# eDuinoUno.net
KiCad netlist of a schematic drawn in EAGLE
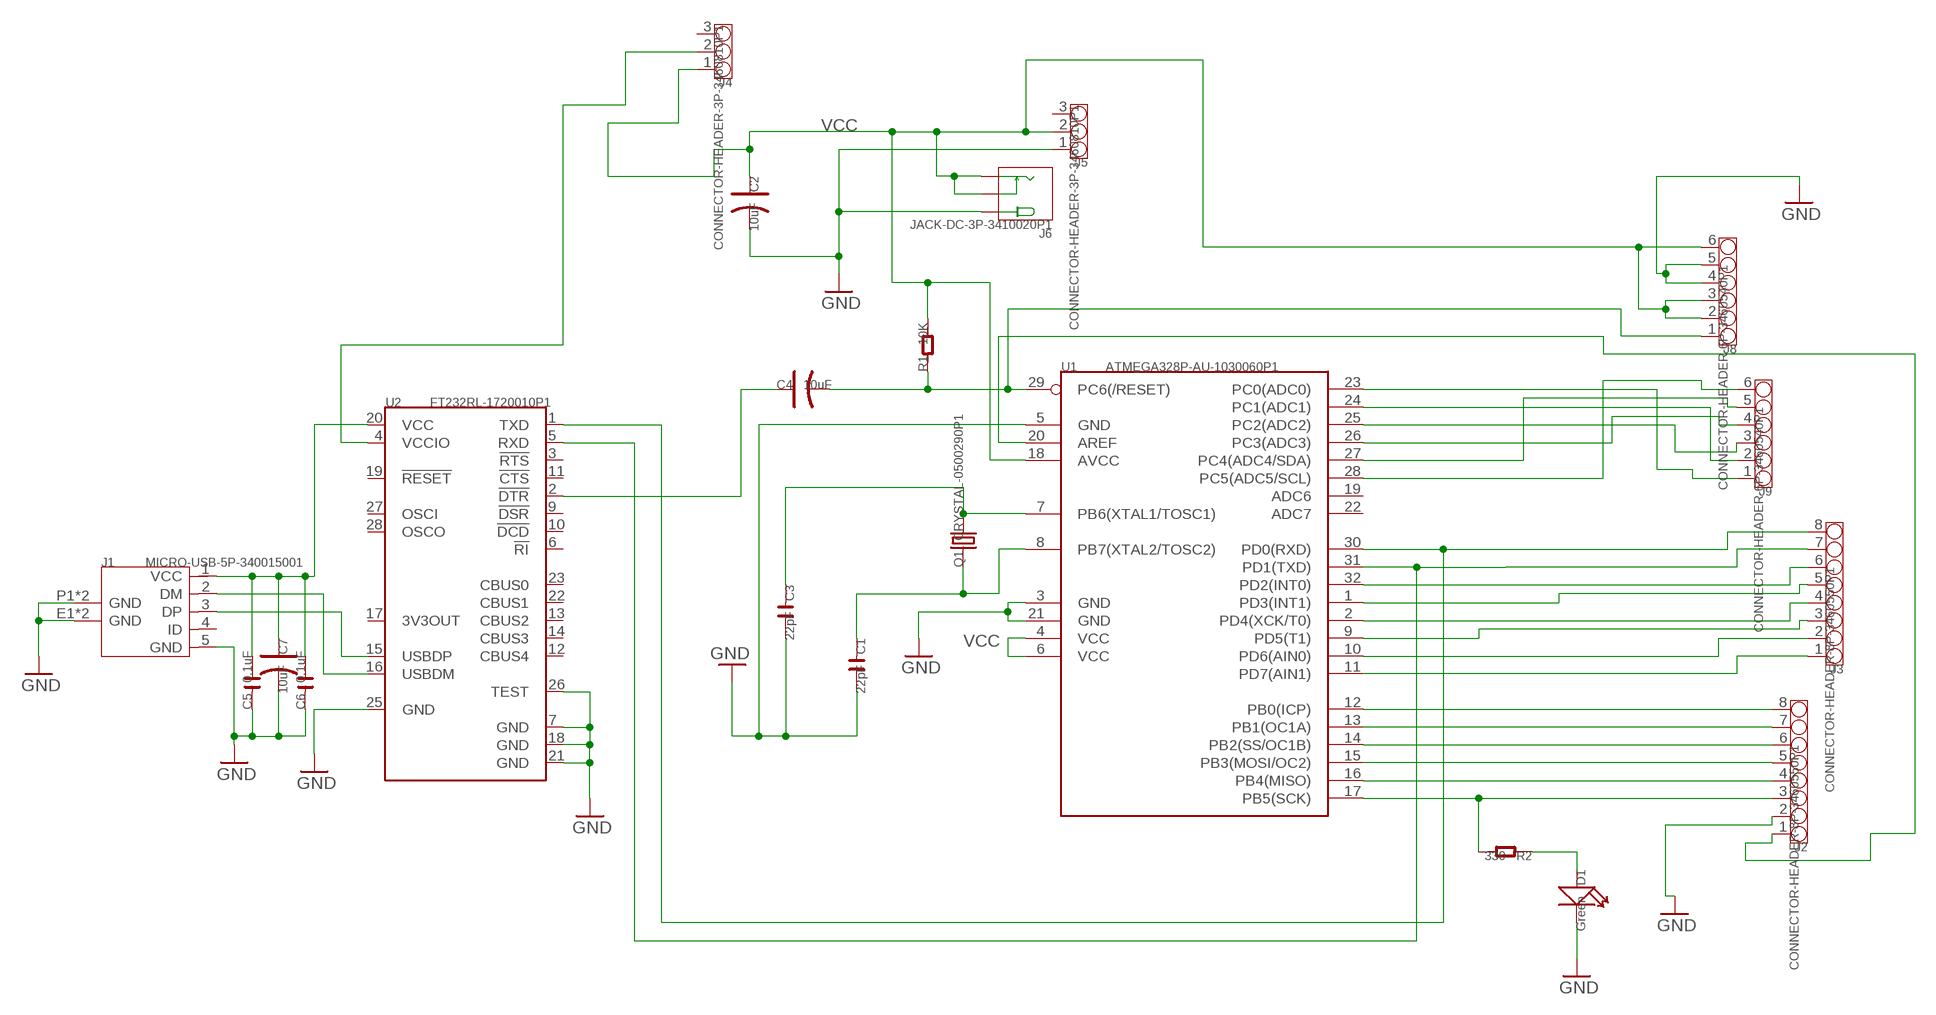
[diagram p0: schematic, sheet 1]

(export (version "E")
  (design (tool "Eeschema 10.0.6"))
  (components
    (comp (ref "C1")
      (value "22pF")
      (footprint "eagle-import:C0603")
      (libsource (lib "eagle-import") (part "C-0603"))
    )
    (comp (ref "C2")
      (value "10uF")
      (footprint "eagle-import:AVX-A")
      (libsource (lib "eagle-import") (part "C-POLAR-A"))
    )
    (comp (ref "C3")
      (value "22pF")
      (footprint "eagle-import:C0603")
      (libsource (lib "eagle-import") (part "C-0603"))
    )
    (comp (ref "C4")
      (value "10uF")
      (footprint "eagle-import:AVX-A")
      (libsource (lib "eagle-import") (part "C-POLAR-A"))
    )
    (comp (ref "C5")
      (value "0.1uF")
      (footprint "eagle-import:C0603")
      (libsource (lib "eagle-import") (part "C-0603"))
    )
    (comp (ref "C6")
      (value "0.1uF")
      (footprint "eagle-import:C0603")
      (libsource (lib "eagle-import") (part "C-0603"))
    )
    (comp (ref "C7")
      (value "10uF")
      (footprint "eagle-import:AVX-A")
      (libsource (lib "eagle-import") (part "C-POLAR-A"))
    )
    (comp (ref "D1")
      (value "Green")
      (footprint "eagle-import:LED0603")
      (libsource (lib "eagle-import") (part "LED"))
    )
    (comp (ref "J1")
      (value "MICRO-USB-5P-340015001")
      (footprint "eagle-import:B-SMD-5P")
      (libsource (lib "eagle-import") (part "MICRO-USB-5P-340015001"))
    )
    (comp (ref "J2")
      (value "CONNECTOR-HEADER-8P-3460550P1")
      (footprint "eagle-import:1X8P-2.54-8.5-WHITE-FEMALE")
      (libsource (lib "eagle-import") (part "CONNECTOR-HEADER-8P-3460550P1"))
    )
    (comp (ref "J3")
      (value "CONNECTOR-HEADER-8P-3460550P1")
      (footprint "eagle-import:1X8P-2.54-8.5-WHITE-FEMALE")
      (libsource (lib "eagle-import") (part "CONNECTOR-HEADER-8P-3460550P1"))
    )
    (comp (ref "J4")
      (value "CONNECTOR-HEADER-3P-3460810P1")
      (footprint "eagle-import:1X3P-2.54-2.54-11.6-3.0-BLACK-MALE")
      (libsource (lib "eagle-import") (part "CONNECTOR-HEADER-3P-3460810P1"))
    )
    (comp (ref "J5")
      (value "CONNECTOR-HEADER-3P-3460810P1")
      (footprint "eagle-import:1X3P-2.54-2.54-11.6-3.0-BLACK-MALE")
      (libsource (lib "eagle-import") (part "CONNECTOR-HEADER-3P-3460810P1"))
    )
    (comp (ref "J6")
      (value "JACK-DC-3P-3410020P1")
      (footprint "eagle-import:PW-3P-2.1")
      (libsource (lib "eagle-import") (part "JACK-DC-3P-3410020P1"))
    )
    (comp (ref "J8")
      (value "CONNECTOR-HEADER-6P-3460540P1")
      (footprint "eagle-import:1X6P-2.54-8.5-WHITE-FEMALE")
      (libsource (lib "eagle-import") (part "CONNECTOR-HEADER-6P-3460540P1"))
    )
    (comp (ref "J9")
      (value "CONNECTOR-HEADER-6P-3460540P1")
      (footprint "eagle-import:1X6P-2.54-8.5-WHITE-FEMALE")
      (libsource (lib "eagle-import") (part "CONNECTOR-HEADER-6P-3460540P1"))
    )
    (comp (ref "Q1")
      (value "CRYSTAL-0500290P1")
      (footprint "eagle-import:2P-SMD-5.0X3.2")
      (libsource (lib "eagle-import") (part "CRYSTAL-0500290P1"))
    )
    (comp (ref "R1")
      (value "10K")
      (footprint "eagle-import:R0603")
      (libsource (lib "eagle-import") (part "R-0603"))
    )
    (comp (ref "R2")
      (value "330")
      (footprint "eagle-import:R0603")
      (libsource (lib "eagle-import") (part "R-0603"))
    )
    (comp (ref "U1")
      (value "ATMEGA328P-AU-1030060P1")
      (footprint "eagle-import:TQFP32")
      (libsource (lib "eagle-import") (part "ATMEGA328P-AU-1030060P1"))
    )
    (comp (ref "U2")
      (value "FT232RL-1720010P1")
      (footprint "eagle-import:SSOP28")
      (libsource (lib "eagle-import") (part "FT232RL-1720010P1"))
    )
  )
  (nets
    (net (code "1") (name "/VCC") (class "Default")
      (node (ref "C2") (pin "+") (pinfunction "1_+") (pintype "bidirectional"))
      (node (ref "J4") (pin "1") (pinfunction "1_1") (pintype "bidirectional"))
      (node (ref "J5") (pin "2") (pinfunction "2_2") (pintype "bidirectional"))
      (node (ref "J6") (pin "-1") (pinfunction "-_-1") (pintype "bidirectional"))
      (node (ref "J6") (pin "-2") (pinfunction "CDN_-2") (pintype "bidirectional"))
      (node (ref "J8") (pin "2") (pinfunction "2_2") (pintype "bidirectional"))
      (node (ref "J8") (pin "3") (pinfunction "3_3") (pintype "bidirectional"))
      (node (ref "J8") (pin "6") (pinfunction "6_6") (pintype "bidirectional"))
      (node (ref "R1") (pin "2") (pinfunction "2_2") (pintype "bidirectional"))
      (node (ref "U1") (pin "18") (pinfunction "AVCC_18") (pintype "bidirectional"))
      (node (ref "U1") (pin "4") (pinfunction "VCC_4") (pintype "bidirectional"))
      (node (ref "U1") (pin "6") (pinfunction "VCC_6") (pintype "bidirectional"))
    )
    (net (code "2") (name "GND") (class "Default")
      (node (ref "C1") (pin "2") (pinfunction "2_2") (pintype "bidirectional"))
      (node (ref "C2") (pin "-") (pinfunction "2_-") (pintype "bidirectional"))
      (node (ref "C3") (pin "2") (pinfunction "2_2") (pintype "bidirectional"))
      (node (ref "C5") (pin "1") (pinfunction "1_1") (pintype "bidirectional"))
      (node (ref "C6") (pin "1") (pinfunction "1_1") (pintype "bidirectional"))
      (node (ref "C7") (pin "-") (pinfunction "2_-") (pintype "bidirectional"))
      (node (ref "D1") (pin "-") (pinfunction "-_-") (pintype "passive"))
      (node (ref "J1") (pin "5") (pinfunction "GND_5") (pintype "bidirectional"))
      (node (ref "J1") (pin "E1") (pinfunction "GND_E1") (pintype "bidirectional"))
      (node (ref "J1") (pin "E2") (pinfunction "GND_E2") (pintype "bidirectional"))
      (node (ref "J1") (pin "P1") (pinfunction "GND_P1") (pintype "bidirectional"))
      (node (ref "J1") (pin "P2") (pinfunction "GND_P2") (pintype "bidirectional"))
      (node (ref "J2") (pin "2") (pinfunction "2_2") (pintype "bidirectional"))
      (node (ref "J5") (pin "1") (pinfunction "1_1") (pintype "bidirectional"))
      (node (ref "J6") (pin "+") (pinfunction "+_+") (pintype "bidirectional"))
      (node (ref "J8") (pin "4") (pinfunction "4_4") (pintype "bidirectional"))
      (node (ref "J8") (pin "5") (pinfunction "5_5") (pintype "bidirectional"))
      (node (ref "U1") (pin "21") (pinfunction "GND_21") (pintype "bidirectional"))
      (node (ref "U1") (pin "3") (pinfunction "GND_3") (pintype "bidirectional"))
      (node (ref "U1") (pin "5") (pinfunction "GND_5") (pintype "bidirectional"))
      (node (ref "U2") (pin "18") (pinfunction "GND_18") (pintype "input"))
      (node (ref "U2") (pin "21") (pinfunction "GND_21") (pintype "input"))
      (node (ref "U2") (pin "25") (pinfunction "GND_25") (pintype "input"))
      (node (ref "U2") (pin "26") (pinfunction "TEST_26") (pintype "input"))
      (node (ref "U2") (pin "7") (pinfunction "GND_7") (pintype "input"))
    )
    (net (code "3") (name "Net-(C4-1)") (class "Default")
      (node (ref "C4") (pin "+") (pinfunction "1_+") (pintype "bidirectional"))
      (node (ref "U2") (pin "2") (pinfunction "~{DTR}_2") (pintype "input"))
    )
    (net (code "4") (name "Net-(C4-2)") (class "Default")
      (node (ref "C4") (pin "-") (pinfunction "2_-") (pintype "bidirectional"))
      (node (ref "J8") (pin "1") (pinfunction "1_1") (pintype "bidirectional"))
      (node (ref "R1") (pin "1") (pinfunction "1_1") (pintype "bidirectional"))
      (node (ref "U1") (pin "29") (pinfunction "PC6(/RESET)_29") (pintype "bidirectional"))
    )
    (net (code "5") (name "Net-(C7-1)") (class "Default")
      (node (ref "C5") (pin "2") (pinfunction "2_2") (pintype "bidirectional"))
      (node (ref "C6") (pin "2") (pinfunction "2_2") (pintype "bidirectional"))
      (node (ref "C7") (pin "+") (pinfunction "1_+") (pintype "bidirectional"))
      (node (ref "J1") (pin "1") (pinfunction "VCC_1") (pintype "bidirectional"))
      (node (ref "U2") (pin "20") (pinfunction "VCC_20") (pintype "input"))
    )
    (net (code "6") (name "Net-(D1-Pad+)") (class "Default")
      (node (ref "D1") (pin "+") (pinfunction "+_+") (pintype "passive"))
      (node (ref "R2") (pin "1") (pinfunction "1_1") (pintype "bidirectional"))
    )
    (net (code "7") (name "Net-(J1-DM)") (class "Default")
      (node (ref "J1") (pin "2") (pinfunction "DM_2") (pintype "bidirectional"))
      (node (ref "U2") (pin "16") (pinfunction "USBDM_16") (pintype "input"))
    )
    (net (code "8") (name "Net-(J1-DP)") (class "Default")
      (node (ref "J1") (pin "3") (pinfunction "DP_3") (pintype "bidirectional"))
      (node (ref "U2") (pin "15") (pinfunction "USBDP_15") (pintype "input"))
    )
    (net (code "9") (name "Net-(U1-AREF)") (class "Default")
      (node (ref "J2") (pin "1") (pinfunction "1_1") (pintype "bidirectional"))
      (node (ref "U1") (pin "20") (pinfunction "AREF_20") (pintype "bidirectional"))
    )
    (net (code "10") (name "Net-(U1-PB0(ICP))") (class "Default")
      (node (ref "J2") (pin "8") (pinfunction "8_8") (pintype "bidirectional"))
      (node (ref "U1") (pin "12") (pinfunction "PB0(ICP)_12") (pintype "bidirectional"))
    )
    (net (code "11") (name "Net-(U1-PB1(OC1A))") (class "Default")
      (node (ref "J2") (pin "7") (pinfunction "7_7") (pintype "bidirectional"))
      (node (ref "U1") (pin "13") (pinfunction "PB1(OC1A)_13") (pintype "bidirectional"))
    )
    (net (code "12") (name "Net-(U1-PB2(SS{slash}OC1B))") (class "Default")
      (node (ref "J2") (pin "6") (pinfunction "6_6") (pintype "bidirectional"))
      (node (ref "U1") (pin "14") (pinfunction "PB2(SS/OC1B)_14") (pintype "bidirectional"))
    )
    (net (code "13") (name "Net-(U1-PB3(MOSI{slash}OC2))") (class "Default")
      (node (ref "J2") (pin "5") (pinfunction "5_5") (pintype "bidirectional"))
      (node (ref "U1") (pin "15") (pinfunction "PB3(MOSI/OC2)_15") (pintype "bidirectional"))
    )
    (net (code "14") (name "Net-(U1-PB4(MISO))") (class "Default")
      (node (ref "J2") (pin "4") (pinfunction "4_4") (pintype "bidirectional"))
      (node (ref "U1") (pin "16") (pinfunction "PB4(MISO)_16") (pintype "bidirectional"))
    )
    (net (code "15") (name "Net-(U1-PB5(SCK))") (class "Default")
      (node (ref "J2") (pin "3") (pinfunction "3_3") (pintype "bidirectional"))
      (node (ref "R2") (pin "2") (pinfunction "2_2") (pintype "bidirectional"))
      (node (ref "U1") (pin "17") (pinfunction "PB5(SCK)_17") (pintype "bidirectional"))
    )
    (net (code "16") (name "Net-(U1-PB6(XTAL1{slash}TOSC1))") (class "Default")
      (node (ref "C3") (pin "1") (pinfunction "1_1") (pintype "bidirectional"))
      (node (ref "Q1") (pin "2") (pinfunction "2_2") (pintype "passive"))
      (node (ref "U1") (pin "7") (pinfunction "PB6(XTAL1/TOSC1)_7") (pintype "bidirectional"))
    )
    (net (code "17") (name "Net-(U1-PB7(XTAL2{slash}TOSC2))") (class "Default")
      (node (ref "C1") (pin "1") (pinfunction "1_1") (pintype "bidirectional"))
      (node (ref "Q1") (pin "1") (pinfunction "1_1") (pintype "passive"))
      (node (ref "U1") (pin "8") (pinfunction "PB7(XTAL2/TOSC2)_8") (pintype "bidirectional"))
    )
    (net (code "18") (name "Net-(U1-PC0(ADC0))") (class "Default")
      (node (ref "J9") (pin "1") (pinfunction "1_1") (pintype "bidirectional"))
      (node (ref "U1") (pin "23") (pinfunction "PC0(ADC0)_23") (pintype "bidirectional"))
    )
    (net (code "19") (name "Net-(U1-PC1(ADC1))") (class "Default")
      (node (ref "J9") (pin "2") (pinfunction "2_2") (pintype "bidirectional"))
      (node (ref "U1") (pin "24") (pinfunction "PC1(ADC1)_24") (pintype "bidirectional"))
    )
    (net (code "20") (name "Net-(U1-PC2(ADC2))") (class "Default")
      (node (ref "J9") (pin "3") (pinfunction "3_3") (pintype "bidirectional"))
      (node (ref "U1") (pin "25") (pinfunction "PC2(ADC2)_25") (pintype "bidirectional"))
    )
    (net (code "21") (name "Net-(U1-PC3(ADC3))") (class "Default")
      (node (ref "J9") (pin "4") (pinfunction "4_4") (pintype "bidirectional"))
      (node (ref "U1") (pin "26") (pinfunction "PC3(ADC3)_26") (pintype "bidirectional"))
    )
    (net (code "22") (name "Net-(U1-PC4(ADC4{slash}SDA))") (class "Default")
      (node (ref "J9") (pin "5") (pinfunction "5_5") (pintype "bidirectional"))
      (node (ref "U1") (pin "27") (pinfunction "PC4(ADC4/SDA)_27") (pintype "bidirectional"))
    )
    (net (code "23") (name "Net-(U1-PC5(ADC5{slash}SCL))") (class "Default")
      (node (ref "J9") (pin "6") (pinfunction "6_6") (pintype "bidirectional"))
      (node (ref "U1") (pin "28") (pinfunction "PC5(ADC5/SCL)_28") (pintype "bidirectional"))
    )
    (net (code "24") (name "Net-(U1-PD0(RXD))") (class "Default")
      (node (ref "J3") (pin "8") (pinfunction "8_8") (pintype "bidirectional"))
      (node (ref "U1") (pin "30") (pinfunction "PD0(RXD)_30") (pintype "bidirectional"))
      (node (ref "U2") (pin "1") (pinfunction "TXD_1") (pintype "input"))
    )
    (net (code "25") (name "Net-(U1-PD1(TXD))") (class "Default")
      (node (ref "J3") (pin "7") (pinfunction "7_7") (pintype "bidirectional"))
      (node (ref "U1") (pin "31") (pinfunction "PD1(TXD)_31") (pintype "bidirectional"))
      (node (ref "U2") (pin "5") (pinfunction "RXD_5") (pintype "input"))
    )
    (net (code "26") (name "Net-(U1-PD2(INT0))") (class "Default")
      (node (ref "J3") (pin "6") (pinfunction "6_6") (pintype "bidirectional"))
      (node (ref "U1") (pin "32") (pinfunction "PD2(INT0)_32") (pintype "bidirectional"))
    )
    (net (code "27") (name "Net-(U1-PD3(INT1))") (class "Default")
      (node (ref "J3") (pin "5") (pinfunction "5_5") (pintype "bidirectional"))
      (node (ref "U1") (pin "1") (pinfunction "PD3(INT1)_1") (pintype "bidirectional"))
    )
    (net (code "28") (name "Net-(U1-PD4(XCK{slash}T0))") (class "Default")
      (node (ref "J3") (pin "4") (pinfunction "4_4") (pintype "bidirectional"))
      (node (ref "U1") (pin "2") (pinfunction "PD4(XCK/T0)_2") (pintype "bidirectional"))
    )
    (net (code "29") (name "Net-(U1-PD5(T1))") (class "Default")
      (node (ref "J3") (pin "3") (pinfunction "3_3") (pintype "bidirectional"))
      (node (ref "U1") (pin "9") (pinfunction "PD5(T1)_9") (pintype "bidirectional"))
    )
    (net (code "30") (name "Net-(U1-PD6(AIN0))") (class "Default")
      (node (ref "J3") (pin "2") (pinfunction "2_2") (pintype "bidirectional"))
      (node (ref "U1") (pin "10") (pinfunction "PD6(AIN0)_10") (pintype "bidirectional"))
    )
    (net (code "31") (name "Net-(U1-PD7(AIN1))") (class "Default")
      (node (ref "J3") (pin "1") (pinfunction "1_1") (pintype "bidirectional"))
      (node (ref "U1") (pin "11") (pinfunction "PD7(AIN1)_11") (pintype "bidirectional"))
    )
    (net (code "32") (name "Net-(U2-VCCIO)") (class "Default")
      (node (ref "J4") (pin "2") (pinfunction "2_2") (pintype "bidirectional"))
      (node (ref "U2") (pin "4") (pinfunction "VCCIO_4") (pintype "input"))
    )
    (net (code "33") (name "unconnected-(J1-ID-Pad4)") (class "Default")
      (node (ref "J1") (pin "4") (pinfunction "ID_4") (pintype "bidirectional"))
    )
    (net (code "34") (name "unconnected-(J4-Pad3)") (class "Default")
      (node (ref "J4") (pin "3") (pinfunction "3_3") (pintype "bidirectional"))
    )
    (net (code "35") (name "unconnected-(J5-Pad3)") (class "Default")
      (node (ref "J5") (pin "3") (pinfunction "3_3") (pintype "bidirectional"))
    )
    (net (code "36") (name "unconnected-(U1-ADC6-Pad19)") (class "Default")
      (node (ref "U1") (pin "19") (pinfunction "ADC6_19") (pintype "bidirectional"))
    )
    (net (code "37") (name "unconnected-(U1-ADC7-Pad22)") (class "Default")
      (node (ref "U1") (pin "22") (pinfunction "ADC7_22") (pintype "bidirectional"))
    )
    (net (code "38") (name "unconnected-(U2-3V3OUT-Pad17)") (class "Default")
      (node (ref "U2") (pin "17") (pinfunction "3V3OUT_17") (pintype "input"))
    )
    (net (code "39") (name "unconnected-(U2-CBUS0-Pad23)") (class "Default")
      (node (ref "U2") (pin "23") (pinfunction "CBUS0_23") (pintype "input"))
    )
    (net (code "40") (name "unconnected-(U2-CBUS1-Pad22)") (class "Default")
      (node (ref "U2") (pin "22") (pinfunction "CBUS1_22") (pintype "input"))
    )
    (net (code "41") (name "unconnected-(U2-CBUS2-Pad13)") (class "Default")
      (node (ref "U2") (pin "13") (pinfunction "CBUS2_13") (pintype "input"))
    )
    (net (code "42") (name "unconnected-(U2-CBUS3-Pad14)") (class "Default")
      (node (ref "U2") (pin "14") (pinfunction "CBUS3_14") (pintype "input"))
    )
    (net (code "43") (name "unconnected-(U2-CBUS4-Pad12)") (class "Default")
      (node (ref "U2") (pin "12") (pinfunction "CBUS4_12") (pintype "input"))
    )
    (net (code "44") (name "unconnected-(U2-OSCI-Pad27)") (class "Default")
      (node (ref "U2") (pin "27") (pinfunction "OSCI_27") (pintype "input"))
    )
    (net (code "45") (name "unconnected-(U2-OSCO-Pad28)") (class "Default")
      (node (ref "U2") (pin "28") (pinfunction "OSCO_28") (pintype "input"))
    )
    (net (code "46") (name "unconnected-(U2-~{CTS}-Pad11)") (class "Default")
      (node (ref "U2") (pin "11") (pinfunction "~{CTS}_11") (pintype "input"))
    )
    (net (code "47") (name "unconnected-(U2-~{DCD}-Pad10)") (class "Default")
      (node (ref "U2") (pin "10") (pinfunction "~{DCD}_10") (pintype "input"))
    )
    (net (code "48") (name "unconnected-(U2-~{DSR}-Pad9)") (class "Default")
      (node (ref "U2") (pin "9") (pinfunction "~{DSR}_9") (pintype "input"))
    )
    (net (code "49") (name "unconnected-(U2-~{RESET}-Pad19)") (class "Default")
      (node (ref "U2") (pin "19") (pinfunction "~{RESET}_19") (pintype "input"))
    )
    (net (code "50") (name "unconnected-(U2-~{RI}-Pad6)") (class "Default")
      (node (ref "U2") (pin "6") (pinfunction "~{RI}_6") (pintype "input"))
    )
    (net (code "51") (name "unconnected-(U2-~{RTS}-Pad3)") (class "Default")
      (node (ref "U2") (pin "3") (pinfunction "~{RTS}_3") (pintype "input"))
    )
  )
)
